# 12_-CAMERA_POWER.net
KiCad netlist of a schematic drawn in Altium Designer
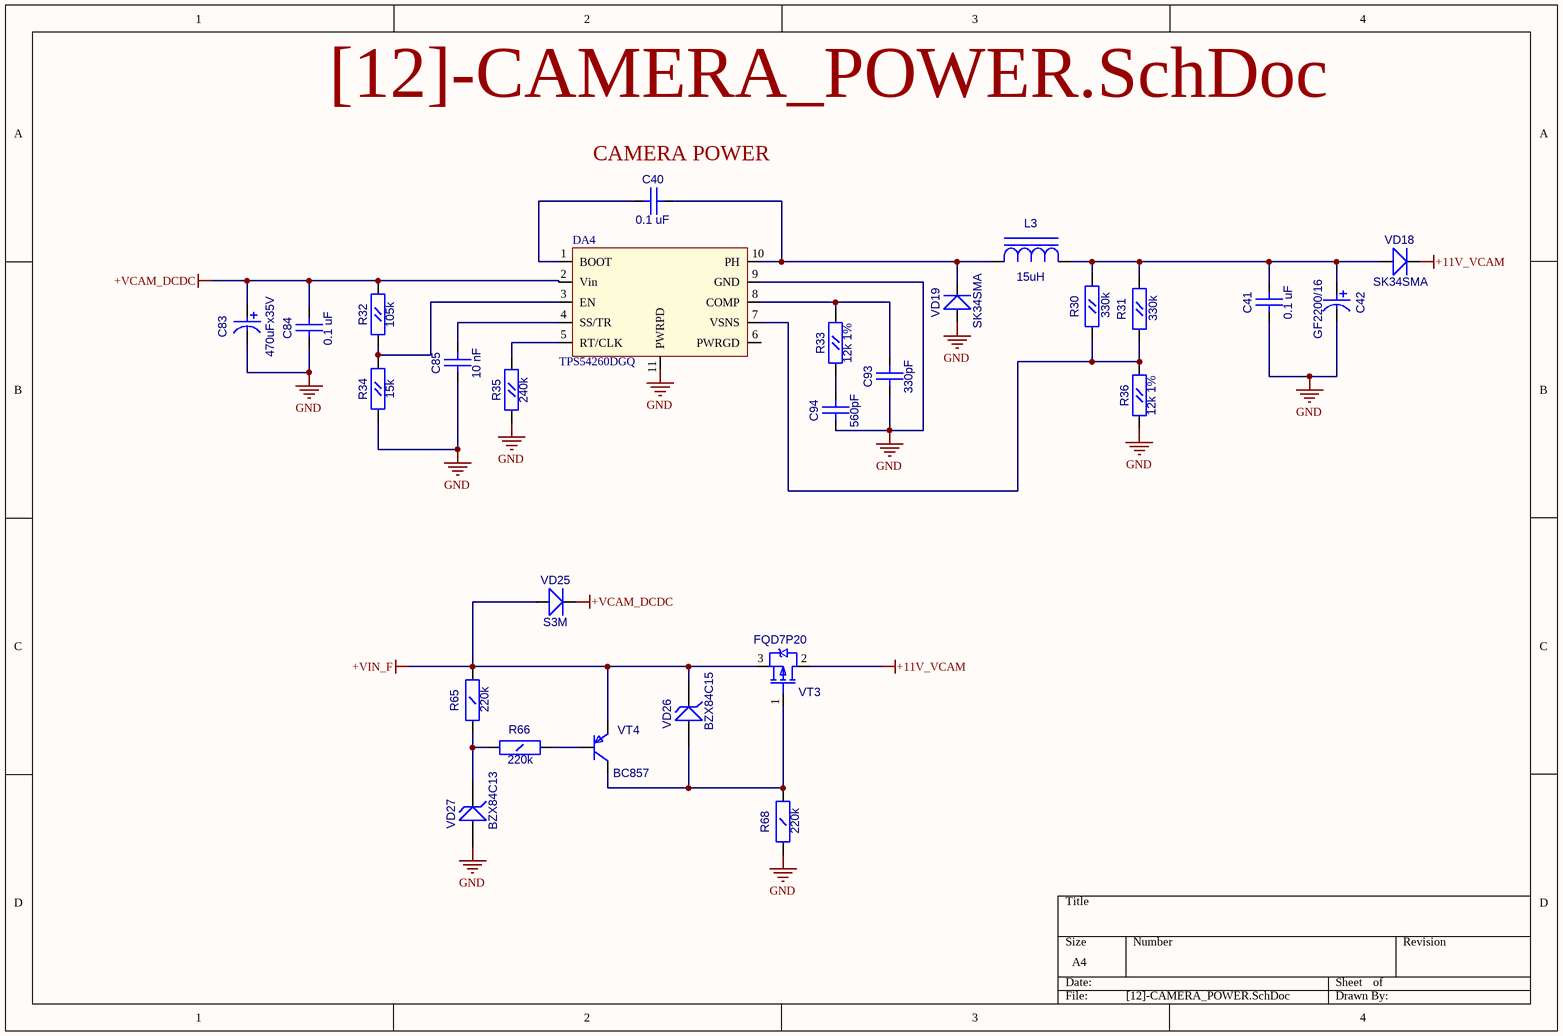
[diagram p0: [12]-CAMERA_POWER.SchDoc]

(export (version "E")
  (design (tool "Eeschema 10.0.6"))
  (components
    (comp (ref "C40")
      (value "0.1 uF")
      (footprint "CC0603")
      (description "CC0603")
      (libsource (lib "gprs_modem_2") (part "CC0603"))
    )
    (comp (ref "C41")
      (value "0.1 uF")
      (footprint "CC0603")
      (description "CC0603")
      (libsource (lib "gprs_modem_2") (part "CC0603"))
    )
    (comp (ref "C42")
      (value "GF2200/16")
      (footprint "CAP10x20_FLAT")
      (description "Radial capacitor")
      (libsource (lib "fizik_lib (1)") (part "CAP_10mm"))
    )
    (comp (ref "C83")
      (value "470uFx35V")
      (footprint "CC16X10_CAP0.5(1)(Primary)")
      (description "CAP0.5(1)")
      (libsource (lib "gprs_modem_2") (part "CAP0.5(1)"))
    )
    (comp (ref "C84")
      (value "0.1 uF")
      (footprint "CC0603")
      (description "CC0603")
      (libsource (lib "gprs_modem_2") (part "CC0603"))
    )
    (comp (ref "C85")
      (value "10 nF")
      (footprint "CC0603")
      (description "CC0603")
      (libsource (lib "gprs_modem_2") (part "CC0603"))
    )
    (comp (ref "C93")
      (value "330pF")
      (footprint "CC0603")
      (description "CC0603")
      (libsource (lib "gprs_modem_2") (part "CC0603"))
    )
    (comp (ref "C94")
      (value "560pF")
      (footprint "CC0603")
      (description "CC0603")
      (libsource (lib "gprs_modem_2") (part "CC0603"))
    )
    (comp (ref "DA4")
      (value "TPS54260DGQ")
      (footprint "S-PDSO-G10")
      (libsource (lib "gprs_modem_2") (part "TPS54260DGQ"))
    )
    (comp (ref "L3")
      (value "15uH")
      (footprint "SDR0805")
      (description "SDR0805")
      (libsource (lib "gprs_modem_2") (part "SDR0805"))
    )
    (comp (ref "R30")
      (value "330k")
      (footprint "RC0603")
      (description "RC0603")
      (libsource (lib "fizik_lib") (part "RC0603"))
    )
    (comp (ref "R31")
      (value "330k")
      (footprint "RC0603")
      (description "RC0603")
      (libsource (lib "fizik_lib") (part "RC0603"))
    )
    (comp (ref "R32")
      (value "105k")
      (footprint "RC0603")
      (description "RC0603")
      (libsource (lib "gprs_modem_2") (part "RC0603"))
    )
    (comp (ref "R33")
      (value "12k 1%")
      (footprint "RC0603")
      (description "RC0603")
      (libsource (lib "gprs_modem_2") (part "RC0603"))
    )
    (comp (ref "R34")
      (value "15k")
      (footprint "RC0603")
      (description "RC0603")
      (libsource (lib "gprs_modem_2") (part "RC0603"))
    )
    (comp (ref "R35")
      (value "240k")
      (footprint "RC0603")
      (description "RC0603")
      (libsource (lib "gprs_modem_2") (part "RC0603"))
    )
    (comp (ref "R36")
      (value "12k 1%")
      (footprint "RC0603")
      (description "RC0603")
      (libsource (lib "gprs_modem_2") (part "RC0603"))
    )
    (comp (ref "R65")
      (value "220k")
      (footprint "RC1206")
      (description "RC1206")
      (libsource (lib "fizik_lib") (part "RC1206"))
    )
    (comp (ref "R66")
      (value "220k")
      (footprint "RC1206")
      (description "RC1206")
      (libsource (lib "fizik_lib") (part "RC1206"))
    )
    (comp (ref "R68")
      (value "220k")
      (footprint "RC1206")
      (description "RC1206")
      (libsource (lib "fizik_lib") (part "RC1206"))
    )
    (comp (ref "VD18")
      (value "SK34SMA")
      (footprint "SMA")
      (description "Schottky Rectifier")
      (libsource (lib "gprs_modem") (part "SK34SMA"))
    )
    (comp (ref "VD19")
      (value "SK34SMA")
      (footprint "SMA")
      (description "Schottky Rectifier")
      (libsource (lib "gprs_modem") (part "SK34SMA"))
    )
    (comp (ref "VD25")
      (value "S3M")
      (footprint "SMC")
      (description "Schottky Rectifier")
      (libsource (lib "fizik_lib") (part "S3A"))
    )
    (comp (ref "VD26")
      (value "BZX84C15")
      (footprint "SOT-23(123)")
      (description "Zener Voltage Regulator Diode")
      (libsource (lib "fizik_lib") (part "BZX84"))
    )
    (comp (ref "VD27")
      (value "BZX84C13")
      (footprint "SOT-23(123)")
      (description "Zener Voltage Regulator Diode")
      (libsource (lib "fizik_lib") (part "BZX84"))
    )
    (comp (ref "VT3")
      (value "FQD7P20")
      (footprint "D-PAK(TO-252AA)")
      (description "HEXFET Power MOSFET")
      (libsource (lib "gprs_modem_2") (part "IRFR9220"))
    )
    (comp (ref "VT4")
      (value "BC857")
      (footprint "SOT-23(123)")
      (description "PNP 100ma transistor")
      (libsource (lib "gprs_modem_2") (part "BC857B"))
    )
  )
  (nets
    (net (code "1") (name "+11V_VCAM") (class "Default")
      (node (ref "VD18") (pin "2") (pinfunction "K_2") (pintype "passive"))
      (node (ref "VT3") (pin "2") (pinfunction "D_2") (pintype "passive"))
    )
    (net (code "2") (name "+VCAM_DCDC") (class "Default")
      (node (ref "C83") (pin "2") (pintype "passive"))
      (node (ref "C84") (pin "1") (pinfunction "A_1") (pintype "passive"))
      (node (ref "DA4") (pin "2") (pinfunction "Vin_2") (pintype "passive"))
      (node (ref "R32") (pin "2") (pinfunction "B_2") (pintype "passive"))
      (node (ref "VD25") (pin "2") (pinfunction "K_2") (pintype "passive"))
    )
    (net (code "3") (name "+VIN_F") (class "Default")
      (node (ref "R65") (pin "2") (pinfunction "B_2") (pintype "passive"))
      (node (ref "VD25") (pin "1") (pinfunction "A_1") (pintype "passive"))
      (node (ref "VD26") (pin "3") (pinfunction "K_3") (pintype "passive"))
      (node (ref "VT3") (pin "3") (pinfunction "S_3") (pintype "passive"))
      (node (ref "VT4") (pin "2") (pinfunction "E_2") (pintype "passive"))
    )
    (net (code "4") (name "GND") (class "Default")
      (node (ref "C41") (pin "2") (pinfunction "B_2") (pintype "passive"))
      (node (ref "C42") (pin "1") (pintype "passive"))
      (node (ref "C83") (pin "1") (pintype "passive"))
      (node (ref "C84") (pin "2") (pinfunction "B_2") (pintype "passive"))
      (node (ref "C85") (pin "2") (pinfunction "B_2") (pintype "passive"))
      (node (ref "C93") (pin "2") (pinfunction "B_2") (pintype "passive"))
      (node (ref "C94") (pin "2") (pinfunction "B_2") (pintype "passive"))
      (node (ref "DA4") (pin "11") (pinfunction "PWRPD_11") (pintype "passive"))
      (node (ref "DA4") (pin "9") (pinfunction "GND_9") (pintype "passive"))
      (node (ref "R34") (pin "1") (pinfunction "A_1") (pintype "passive"))
      (node (ref "R35") (pin "1") (pinfunction "A_1") (pintype "passive"))
      (node (ref "R36") (pin "1") (pinfunction "A_1") (pintype "passive"))
      (node (ref "R68") (pin "1") (pinfunction "A_1") (pintype "passive"))
      (node (ref "VD19") (pin "1") (pinfunction "A_1") (pintype "passive"))
      (node (ref "VD27") (pin "1") (pinfunction "A_1") (pintype "passive"))
    )
    (net (code "5") (name "Net-(C40-A)") (class "Default")
      (node (ref "C40") (pin "1") (pinfunction "A_1") (pintype "passive"))
      (node (ref "DA4") (pin "10") (pinfunction "PH_10") (pintype "passive"))
      (node (ref "L3") (pin "1") (pinfunction "C_1") (pintype "passive"))
      (node (ref "VD19") (pin "2") (pinfunction "K_2") (pintype "passive"))
    )
    (net (code "6") (name "Net-(C40-B)") (class "Default")
      (node (ref "C40") (pin "2") (pinfunction "B_2") (pintype "passive"))
      (node (ref "DA4") (pin "1") (pinfunction "BOOT_1") (pintype "passive"))
    )
    (net (code "7") (name "Net-(C41-A)") (class "Default")
      (node (ref "C41") (pin "1") (pinfunction "A_1") (pintype "passive"))
      (node (ref "C42") (pin "2") (pintype "passive"))
      (node (ref "L3") (pin "2") (pinfunction "A_2") (pintype "passive"))
      (node (ref "R30") (pin "2") (pinfunction "B_2") (pintype "passive"))
      (node (ref "R31") (pin "2") (pinfunction "B_2") (pintype "passive"))
      (node (ref "VD18") (pin "1") (pinfunction "A_1") (pintype "passive"))
    )
    (net (code "8") (name "Net-(C85-A)") (class "Default")
      (node (ref "C85") (pin "1") (pinfunction "A_1") (pintype "passive"))
      (node (ref "DA4") (pin "4") (pinfunction "SS/TR_4") (pintype "passive"))
    )
    (net (code "9") (name "Net-(C93-A)") (class "Default")
      (node (ref "C93") (pin "1") (pinfunction "A_1") (pintype "passive"))
      (node (ref "DA4") (pin "8") (pinfunction "COMP_8") (pintype "passive"))
      (node (ref "R33") (pin "2") (pinfunction "B_2") (pintype "passive"))
    )
    (net (code "10") (name "Net-(C94-A)") (class "Default")
      (node (ref "C94") (pin "1") (pinfunction "A_1") (pintype "passive"))
      (node (ref "R33") (pin "1") (pinfunction "A_1") (pintype "passive"))
    )
    (net (code "11") (name "Net-(DA4-EN)") (class "Default")
      (node (ref "DA4") (pin "3") (pinfunction "EN_3") (pintype "passive"))
      (node (ref "R32") (pin "1") (pinfunction "A_1") (pintype "passive"))
      (node (ref "R34") (pin "2") (pinfunction "B_2") (pintype "passive"))
    )
    (net (code "12") (name "Net-(DA4-RT{slash}CLK)") (class "Default")
      (node (ref "DA4") (pin "5") (pinfunction "RT/CLK_5") (pintype "passive"))
      (node (ref "R35") (pin "2") (pinfunction "B_2") (pintype "passive"))
    )
    (net (code "13") (name "Net-(DA4-VSNS)") (class "Default")
      (node (ref "DA4") (pin "7") (pinfunction "VSNS_7") (pintype "passive"))
      (node (ref "R30") (pin "1") (pinfunction "A_1") (pintype "passive"))
      (node (ref "R31") (pin "1") (pinfunction "A_1") (pintype "passive"))
      (node (ref "R36") (pin "2") (pinfunction "B_2") (pintype "passive"))
    )
    (net (code "14") (name "Net-(R65-A)") (class "Default")
      (node (ref "R65") (pin "1") (pinfunction "A_1") (pintype "passive"))
      (node (ref "R66") (pin "1") (pinfunction "A_1") (pintype "passive"))
      (node (ref "VD27") (pin "3") (pinfunction "K_3") (pintype "passive"))
    )
    (net (code "15") (name "Net-(R66-B)") (class "Default")
      (node (ref "R66") (pin "2") (pinfunction "B_2") (pintype "passive"))
      (node (ref "VT4") (pin "1") (pinfunction "B_1") (pintype "passive"))
    )
    (net (code "16") (name "Net-(R68-B)") (class "Default")
      (node (ref "R68") (pin "2") (pinfunction "B_2") (pintype "passive"))
      (node (ref "VD26") (pin "1") (pinfunction "A_1") (pintype "passive"))
      (node (ref "VT3") (pin "1") (pinfunction "G_1") (pintype "passive"))
      (node (ref "VT4") (pin "3") (pinfunction "C_3") (pintype "passive"))
    )
    (net (code "17") (name "unconnected-(DA4-PWRGD-Pad6)") (class "Default")
      (node (ref "DA4") (pin "6") (pinfunction "PWRGD_6") (pintype "passive"))
    )
  )
)
